# STM8S003F3.net
KiCad netlist of a schematic drawn in Altium Designer
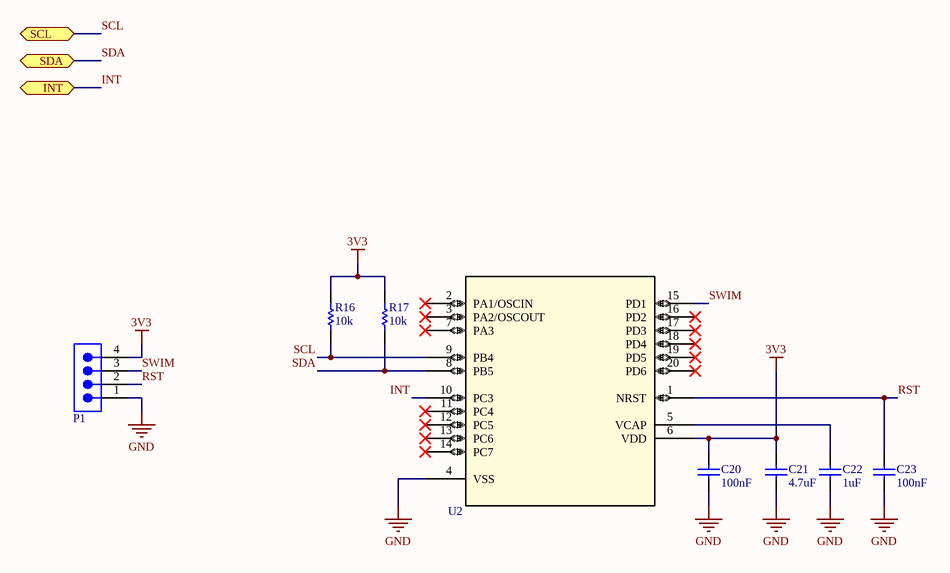
[diagram p0: STM8S003F3.SchDoc]

(export (version "E")
  (design (tool "Eeschema 10.0.6"))
  (components
    (comp (ref "C20")
      (value "100nF")
      (footprint "Wurth 0603 capacitor")
      (fields (field (name "Comment") "Generic Capacitor 100nF 0603"))
      (libsource (lib "Passives") (part "Generic Capacitor 100nF 0603"))
    )
    (comp (ref "C21")
      (value "4.7uF")
      (footprint "Wurth 0603 capacitor")
      (fields (field (name "Comment") "Generic Capacitor 4.7uF 0603"))
      (libsource (lib "Passives") (part "Generic Capacitor 4.7uF 0603"))
    )
    (comp (ref "C22")
      (value "1uF")
      (footprint "Wurth 0603 capacitor")
      (fields (field (name "Comment") "Generic Capacitor 1uF 0603"))
      (libsource (lib "Passives") (part "Generic Capacitor 1uF 0603"))
    )
    (comp (ref "C23")
      (value "100nF")
      (footprint "Wurth 0603 capacitor")
      (fields (field (name "Comment") "Generic Capacitor 100nF 0603"))
      (libsource (lib "Passives") (part "Generic Capacitor 100nF 0603"))
    )
    (comp (ref "P1")
      (value "61300411121")
      (footprint "4x1 2.54mm M")
      (description "WR-PHD Pin Header, THT, Vertical, pitch 2.54mm, 1 Row, 4P")
      (fields (field (name "MANUFACTURER") "Wurth Elektronik"))
      (libsource (lib "2.54mm_pin_headers") (part "4P"))
    )
    (comp (ref "R16")
      (value "10k")
      (footprint "Wurth 0603 Resistor")
      (fields (field (name "Comment") "Generic Resistor 10k 0603"))
      (libsource (lib "Passives") (part "Generic Resistor 10k 0603"))
    )
    (comp (ref "R17")
      (value "10k")
      (footprint "Wurth 0603 Resistor")
      (fields (field (name "Comment") "Generic Resistor 10k 0603"))
      (libsource (lib "Passives") (part "Generic Resistor 10k 0603"))
    )
    (comp (ref "U2")
      (value "STM8S003F3U6TR")
      (footprint "ST UFQFPN20")
      (description "Microcontroller, 8-Bit, FLASH, STM8S CPU, 16MHz, CMOS")
      (fields (field (name "MANUFACTURER") "STMicroelectronics"))
      (libsource (lib "MCU's") (part "STM8S003F3U6TR"))
    )
  )
  (nets
    (net (code "1") (name "/INT") (class "Default")
      (node (ref "U2") (pin "10") (pinfunction "PC3_10") (pintype "bidirectional"))
    )
    (net (code "2") (name "/RST") (class "Default")
      (node (ref "C23") (pin "2") (pinfunction "2_2") (pintype "passive"))
      (node (ref "P1") (pin "2") (pinfunction "2_2") (pintype "passive"))
      (node (ref "U2") (pin "1") (pinfunction "NRST_1") (pintype "bidirectional"))
    )
    (net (code "3") (name "/SCL") (class "Default")
      (node (ref "R16") (pin "1") (pinfunction "1_1") (pintype "passive"))
      (node (ref "U2") (pin "9") (pinfunction "PB4_9") (pintype "bidirectional"))
    )
    (net (code "4") (name "/SDA") (class "Default")
      (node (ref "R17") (pin "1") (pinfunction "1_1") (pintype "passive"))
      (node (ref "U2") (pin "8") (pinfunction "PB5_8") (pintype "bidirectional"))
    )
    (net (code "5") (name "/SWIM") (class "Default")
      (node (ref "P1") (pin "3") (pinfunction "3_3") (pintype "passive"))
      (node (ref "U2") (pin "15") (pinfunction "PD1_15") (pintype "bidirectional"))
    )
    (net (code "6") (name "3V3") (class "Default")
      (node (ref "C20") (pin "2") (pinfunction "2_2") (pintype "passive"))
      (node (ref "C21") (pin "2") (pinfunction "2_2") (pintype "passive"))
      (node (ref "P1") (pin "4") (pinfunction "4_4") (pintype "passive"))
      (node (ref "R16") (pin "2") (pinfunction "2_2") (pintype "passive"))
      (node (ref "R17") (pin "2") (pinfunction "2_2") (pintype "passive"))
      (node (ref "U2") (pin "6") (pinfunction "VDD_6") (pintype "power_in"))
    )
    (net (code "7") (name "GND") (class "Default")
      (node (ref "C20") (pin "1") (pinfunction "1_1") (pintype "passive"))
      (node (ref "C21") (pin "1") (pinfunction "1_1") (pintype "passive"))
      (node (ref "C22") (pin "1") (pinfunction "1_1") (pintype "passive"))
      (node (ref "C23") (pin "1") (pinfunction "1_1") (pintype "passive"))
      (node (ref "P1") (pin "1") (pinfunction "1_1") (pintype "passive"))
      (node (ref "U2") (pin "4") (pinfunction "VSS_4") (pintype "power_in"))
    )
    (net (code "8") (name "Net-(U2-VCAP)") (class "Default")
      (node (ref "C22") (pin "2") (pinfunction "2_2") (pintype "passive"))
      (node (ref "U2") (pin "5") (pinfunction "VCAP_5") (pintype "power_in"))
    )
    (net (code "9") (name "unconnected-(U2-PA1{slash}OSCIN-Pad2)") (class "Default")
      (node (ref "U2") (pin "2") (pinfunction "PA1/OSCIN_2") (pintype "bidirectional+no_connect"))
    )
    (net (code "10") (name "unconnected-(U2-PA2{slash}OSCOUT-Pad3)") (class "Default")
      (node (ref "U2") (pin "3") (pinfunction "PA2/OSCOUT_3") (pintype "bidirectional+no_connect"))
    )
    (net (code "11") (name "unconnected-(U2-PA3-Pad7)") (class "Default")
      (node (ref "U2") (pin "7") (pinfunction "PA3_7") (pintype "bidirectional+no_connect"))
    )
    (net (code "12") (name "unconnected-(U2-PC4-Pad11)") (class "Default")
      (node (ref "U2") (pin "11") (pinfunction "PC4_11") (pintype "bidirectional+no_connect"))
    )
    (net (code "13") (name "unconnected-(U2-PC5-Pad12)") (class "Default")
      (node (ref "U2") (pin "12") (pinfunction "PC5_12") (pintype "bidirectional+no_connect"))
    )
    (net (code "14") (name "unconnected-(U2-PC6-Pad13)") (class "Default")
      (node (ref "U2") (pin "13") (pinfunction "PC6_13") (pintype "bidirectional+no_connect"))
    )
    (net (code "15") (name "unconnected-(U2-PC7-Pad14)") (class "Default")
      (node (ref "U2") (pin "14") (pinfunction "PC7_14") (pintype "bidirectional+no_connect"))
    )
    (net (code "16") (name "unconnected-(U2-PD2-Pad16)") (class "Default")
      (node (ref "U2") (pin "16") (pinfunction "PD2_16") (pintype "bidirectional+no_connect"))
    )
    (net (code "17") (name "unconnected-(U2-PD3-Pad17)") (class "Default")
      (node (ref "U2") (pin "17") (pinfunction "PD3_17") (pintype "bidirectional+no_connect"))
    )
    (net (code "18") (name "unconnected-(U2-PD4-Pad18)") (class "Default")
      (node (ref "U2") (pin "18") (pinfunction "PD4_18") (pintype "bidirectional+no_connect"))
    )
    (net (code "19") (name "unconnected-(U2-PD5-Pad19)") (class "Default")
      (node (ref "U2") (pin "19") (pinfunction "PD5_19") (pintype "bidirectional+no_connect"))
    )
    (net (code "20") (name "unconnected-(U2-PD6-Pad20)") (class "Default")
      (node (ref "U2") (pin "20") (pinfunction "PD6_20") (pintype "bidirectional+no_connect"))
    )
  )
)
